# MTV5Beta.net
KiCad netlist of a schematic drawn in EAGLE
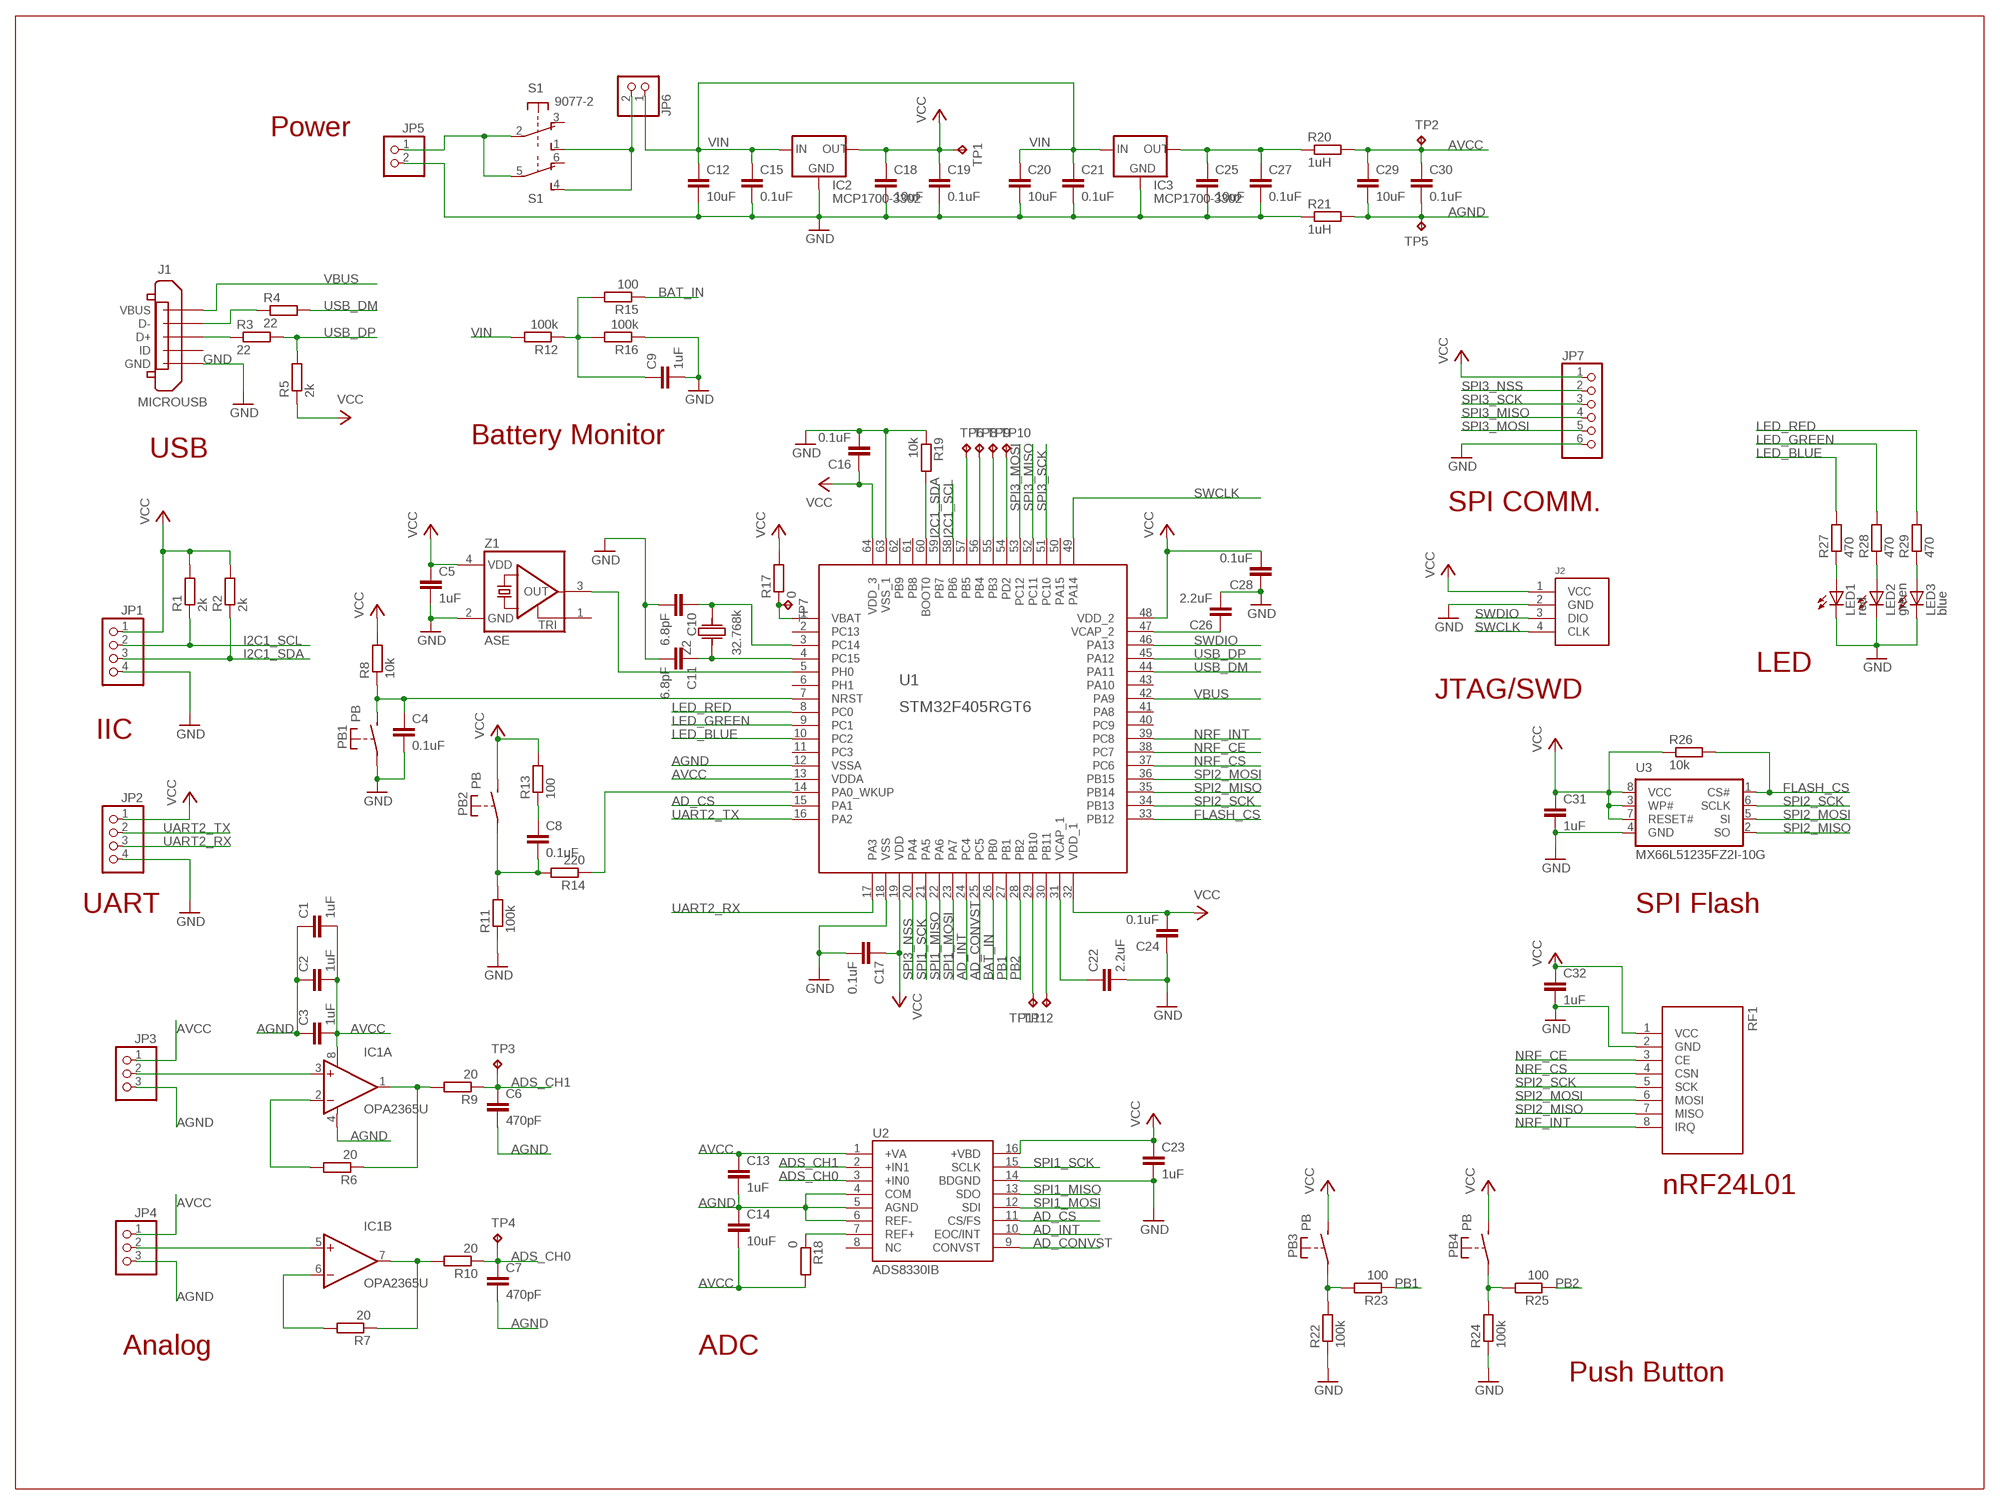
[diagram p0: schematic, sheet 1]

(export (version "E")
  (design (tool "Eeschema 10.0.6"))
  (components
    (comp (ref "C1")
      (value "1uF")
      (footprint "eagle-import:C0603")
      (libsource (lib "eagle-import") (part "C-EUC0603"))
    )
    (comp (ref "C2")
      (value "1uF")
      (footprint "eagle-import:C0603")
      (libsource (lib "eagle-import") (part "C-EUC0603"))
    )
    (comp (ref "C3")
      (value "1uF")
      (footprint "eagle-import:C0603")
      (libsource (lib "eagle-import") (part "C-EUC0603"))
    )
    (comp (ref "C4")
      (value "0.1uF")
      (footprint "eagle-import:C0603")
      (libsource (lib "eagle-import") (part "C-EUC0603"))
    )
    (comp (ref "C5")
      (value "1uF")
      (footprint "eagle-import:C0603")
      (libsource (lib "eagle-import") (part "C-EUC0603"))
    )
    (comp (ref "C6")
      (value "470pF")
      (footprint "eagle-import:C0603")
      (libsource (lib "eagle-import") (part "C-EUC0603"))
    )
    (comp (ref "C7")
      (value "470pF")
      (footprint "eagle-import:C0603")
      (libsource (lib "eagle-import") (part "C-EUC0603"))
    )
    (comp (ref "C8")
      (value "0.1uF")
      (footprint "eagle-import:C0603")
      (libsource (lib "eagle-import") (part "C-EUC0603"))
    )
    (comp (ref "C9")
      (value "1uF")
      (footprint "eagle-import:C0603")
      (libsource (lib "eagle-import") (part "C-EUC0603"))
    )
    (comp (ref "C10")
      (value "6.8pF")
      (footprint "eagle-import:C0603")
      (libsource (lib "eagle-import") (part "C-EUC0603"))
    )
    (comp (ref "C11")
      (value "6.8pF")
      (footprint "eagle-import:C0603")
      (libsource (lib "eagle-import") (part "C-EUC0603"))
    )
    (comp (ref "C12")
      (value "10uF")
      (footprint "eagle-import:C0603")
      (libsource (lib "eagle-import") (part "C-EUC0603"))
    )
    (comp (ref "C13")
      (value "1uF")
      (footprint "eagle-import:C0603")
      (libsource (lib "eagle-import") (part "C-EUC0603"))
    )
    (comp (ref "C14")
      (value "10uF")
      (footprint "eagle-import:C0603")
      (libsource (lib "eagle-import") (part "C-EUC0603"))
    )
    (comp (ref "C15")
      (value "0.1uF")
      (footprint "eagle-import:C0603")
      (libsource (lib "eagle-import") (part "C-EUC0603"))
    )
    (comp (ref "C16")
      (value "0.1uF")
      (footprint "eagle-import:C0603")
      (libsource (lib "eagle-import") (part "C-EUC0603"))
    )
    (comp (ref "C17")
      (value "0.1uF")
      (footprint "eagle-import:C0603")
      (libsource (lib "eagle-import") (part "C-EUC0603"))
    )
    (comp (ref "C18")
      (value "10uF")
      (footprint "eagle-import:C0603")
      (libsource (lib "eagle-import") (part "C-EUC0603"))
    )
    (comp (ref "C19")
      (value "0.1uF")
      (footprint "eagle-import:C0603")
      (libsource (lib "eagle-import") (part "C-EUC0603"))
    )
    (comp (ref "C20")
      (value "10uF")
      (footprint "eagle-import:C0603")
      (libsource (lib "eagle-import") (part "C-EUC0603"))
    )
    (comp (ref "C21")
      (value "0.1uF")
      (footprint "eagle-import:C0603")
      (libsource (lib "eagle-import") (part "C-EUC0603"))
    )
    (comp (ref "C22")
      (value "2.2uF")
      (footprint "eagle-import:C0603")
      (libsource (lib "eagle-import") (part "C-EUC0603"))
    )
    (comp (ref "C23")
      (value "1uF")
      (footprint "eagle-import:C0603")
      (libsource (lib "eagle-import") (part "C-EUC0603"))
    )
    (comp (ref "C24")
      (value "0.1uF")
      (footprint "eagle-import:C0603")
      (libsource (lib "eagle-import") (part "C-EUC0603"))
    )
    (comp (ref "C25")
      (value "10uF")
      (footprint "eagle-import:C0603")
      (libsource (lib "eagle-import") (part "C-EUC0603"))
    )
    (comp (ref "C26")
      (value "2.2uF")
      (footprint "eagle-import:C0603")
      (libsource (lib "eagle-import") (part "C-EUC0603"))
    )
    (comp (ref "C27")
      (value "0.1uF")
      (footprint "eagle-import:C0603")
      (libsource (lib "eagle-import") (part "C-EUC0603"))
    )
    (comp (ref "C28")
      (value "0.1uF")
      (footprint "eagle-import:C0603")
      (libsource (lib "eagle-import") (part "C-EUC0603"))
    )
    (comp (ref "C29")
      (value "10uF")
      (footprint "eagle-import:C0603")
      (libsource (lib "eagle-import") (part "C-EUC0603"))
    )
    (comp (ref "C30")
      (value "0.1uF")
      (footprint "eagle-import:C0603")
      (libsource (lib "eagle-import") (part "C-EUC0603"))
    )
    (comp (ref "C31")
      (value "1uF")
      (footprint "eagle-import:C0603")
      (libsource (lib "eagle-import") (part "C-EUC0603"))
    )
    (comp (ref "C32")
      (value "1uF")
      (footprint "eagle-import:C0603")
      (libsource (lib "eagle-import") (part "C-EUC0603"))
    )
    (comp (ref "IC1")
      (value "OPA2365U")
      (footprint "eagle-import:SO08")
      (fields (field (name "MF") "TEXAS INSTRUMENTS") (field (name "MPN") "OPA2134UA"))
      (libsource (lib "eagle-import") (part "OPA2365U"))
    )
    (comp (ref "IC2")
      (value "MCP1700-3302")
      (footprint "eagle-import:SOT23")
      (libsource (lib "eagle-import") (part "XC63FPM"))
    )
    (comp (ref "IC3")
      (value "MCP1700-3302")
      (footprint "eagle-import:SOT23")
      (libsource (lib "eagle-import") (part "XC63FPM"))
    )
    (comp (ref "J1")
      (value "MICROUSB")
      (footprint "eagle-import:MOLEX47346")
      (libsource (lib "eagle-import") (part "MICROUSB"))
    )
    (comp (ref "J2")
      (value "SWDPORT")
      (footprint "eagle-import:125-4P")
      (libsource (lib "eagle-import") (part "SWDPORT"))
    )
    (comp (ref "JP1")
      (value "PINHD-1X4")
      (footprint "eagle-import:1X04")
      (libsource (lib "eagle-import") (part "PINHD-1X4"))
    )
    (comp (ref "JP2")
      (value "PINHD-1X4")
      (footprint "eagle-import:1X04")
      (libsource (lib "eagle-import") (part "PINHD-1X4"))
    )
    (comp (ref "JP3")
      (value "PINHD-1X3")
      (footprint "eagle-import:1X03")
      (libsource (lib "eagle-import") (part "PINHD-1X3"))
    )
    (comp (ref "JP4")
      (value "PINHD-1X3")
      (footprint "eagle-import:1X03")
      (libsource (lib "eagle-import") (part "PINHD-1X3"))
    )
    (comp (ref "JP5")
      (value "PINHD-1X2")
      (footprint "eagle-import:1X02")
      (libsource (lib "eagle-import") (part "PINHD-1X2"))
    )
    (comp (ref "JP6")
      (value "PINHD-1X2")
      (footprint "eagle-import:1X02")
      (libsource (lib "eagle-import") (part "PINHD-1X2"))
    )
    (comp (ref "JP7")
      (value "PINHD-1X6")
      (footprint "eagle-import:1X06")
      (libsource (lib "eagle-import") (part "PINHD-1X6"))
    )
    (comp (ref "LED1")
      (value "red")
      (footprint "eagle-import:CHIP-LED0805")
      (libsource (lib "eagle-import") (part "LEDCHIP-LED0805"))
    )
    (comp (ref "LED2")
      (value "green")
      (footprint "eagle-import:CHIP-LED0805")
      (libsource (lib "eagle-import") (part "LEDCHIP-LED0805"))
    )
    (comp (ref "LED3")
      (value "blue")
      (footprint "eagle-import:CHIP-LED0805")
      (libsource (lib "eagle-import") (part "LEDCHIP-LED0805"))
    )
    (comp (ref "PB1")
      (value "PB")
      (footprint "eagle-import:BUTTON")
      (libsource (lib "eagle-import") (part "PB"))
    )
    (comp (ref "PB2")
      (value "PB")
      (footprint "eagle-import:BUTTON")
      (libsource (lib "eagle-import") (part "PB"))
    )
    (comp (ref "PB3")
      (value "PB")
      (footprint "eagle-import:BUTTON")
      (libsource (lib "eagle-import") (part "PB"))
    )
    (comp (ref "PB4")
      (value "PB")
      (footprint "eagle-import:BUTTON")
      (libsource (lib "eagle-import") (part "PB"))
    )
    (comp (ref "R1")
      (value "2k")
      (footprint "eagle-import:R0603")
      (libsource (lib "eagle-import") (part "R-EU_R0603"))
    )
    (comp (ref "R2")
      (value "2k")
      (footprint "eagle-import:R0603")
      (libsource (lib "eagle-import") (part "R-EU_R0603"))
    )
    (comp (ref "R3")
      (value "22")
      (footprint "eagle-import:R0603")
      (libsource (lib "eagle-import") (part "R-EU_R0603"))
    )
    (comp (ref "R4")
      (value "22")
      (footprint "eagle-import:R0603")
      (libsource (lib "eagle-import") (part "R-EU_R0603"))
    )
    (comp (ref "R5")
      (value "2k")
      (footprint "eagle-import:R0603")
      (libsource (lib "eagle-import") (part "R-EU_R0603"))
    )
    (comp (ref "R6")
      (value "20")
      (footprint "eagle-import:R0603")
      (libsource (lib "eagle-import") (part "R-EU_R0603"))
    )
    (comp (ref "R7")
      (value "20")
      (footprint "eagle-import:R0603")
      (libsource (lib "eagle-import") (part "R-EU_R0603"))
    )
    (comp (ref "R8")
      (value "10k")
      (footprint "eagle-import:R0603")
      (libsource (lib "eagle-import") (part "R-EU_R0603"))
    )
    (comp (ref "R9")
      (value "20")
      (footprint "eagle-import:R0603")
      (libsource (lib "eagle-import") (part "R-EU_R0603"))
    )
    (comp (ref "R10")
      (value "20")
      (footprint "eagle-import:R0603")
      (libsource (lib "eagle-import") (part "R-EU_R0603"))
    )
    (comp (ref "R11")
      (value "100k")
      (footprint "eagle-import:R0603")
      (libsource (lib "eagle-import") (part "R-EU_R0603"))
    )
    (comp (ref "R12")
      (value "100k")
      (footprint "eagle-import:R0603")
      (libsource (lib "eagle-import") (part "R-EU_R0603"))
    )
    (comp (ref "R13")
      (value "100")
      (footprint "eagle-import:R0603")
      (libsource (lib "eagle-import") (part "R-EU_R0603"))
    )
    (comp (ref "R14")
      (value "220")
      (footprint "eagle-import:R0603")
      (libsource (lib "eagle-import") (part "R-EU_R0603"))
    )
    (comp (ref "R15")
      (value "100")
      (footprint "eagle-import:R0603")
      (libsource (lib "eagle-import") (part "R-EU_R0603"))
    )
    (comp (ref "R16")
      (value "100k")
      (footprint "eagle-import:R0603")
      (libsource (lib "eagle-import") (part "R-EU_R0603"))
    )
    (comp (ref "R17")
      (value "0")
      (footprint "eagle-import:R0603")
      (libsource (lib "eagle-import") (part "R-EU_R0603"))
    )
    (comp (ref "R18")
      (value "0")
      (footprint "eagle-import:R0603")
      (libsource (lib "eagle-import") (part "R-EU_R0603"))
    )
    (comp (ref "R19")
      (value "10k")
      (footprint "eagle-import:R0603")
      (libsource (lib "eagle-import") (part "R-EU_R0603"))
    )
    (comp (ref "R20")
      (value "1uH")
      (footprint "eagle-import:R0603")
      (libsource (lib "eagle-import") (part "R-EU_R0603"))
    )
    (comp (ref "R21")
      (value "1uH")
      (footprint "eagle-import:R0603")
      (libsource (lib "eagle-import") (part "R-EU_R0603"))
    )
    (comp (ref "R22")
      (value "100k")
      (footprint "eagle-import:R0603")
      (libsource (lib "eagle-import") (part "R-EU_R0603"))
    )
    (comp (ref "R23")
      (value "100")
      (footprint "eagle-import:R0603")
      (libsource (lib "eagle-import") (part "R-EU_R0603"))
    )
    (comp (ref "R24")
      (value "100k")
      (footprint "eagle-import:R0603")
      (libsource (lib "eagle-import") (part "R-EU_R0603"))
    )
    (comp (ref "R25")
      (value "100")
      (footprint "eagle-import:R0603")
      (libsource (lib "eagle-import") (part "R-EU_R0603"))
    )
    (comp (ref "R26")
      (value "10k")
      (footprint "eagle-import:R0603")
      (libsource (lib "eagle-import") (part "R-EU_R0603"))
    )
    (comp (ref "R27")
      (value "470")
      (footprint "eagle-import:R0603")
      (libsource (lib "eagle-import") (part "R-EU_R0603"))
    )
    (comp (ref "R28")
      (value "470")
      (footprint "eagle-import:R0603")
      (libsource (lib "eagle-import") (part "R-EU_R0603"))
    )
    (comp (ref "R29")
      (value "470")
      (footprint "eagle-import:R0603")
      (libsource (lib "eagle-import") (part "R-EU_R0603"))
    )
    (comp (ref "RF1")
      (value "NRF24L01")
      (footprint "eagle-import:NRF24L01-MINI")
      (libsource (lib "eagle-import") (part "NRF24L01"))
    )
    (comp (ref "S1")
      (value "9077-2")
      (footprint "eagle-import:9077-2")
      (libsource (lib "eagle-import") (part "9077-2"))
    )
    (comp (ref "TP1")
      (value "TPB1,27")
      (footprint "eagle-import:B1,27")
      (libsource (lib "eagle-import") (part "TPB1,27"))
    )
    (comp (ref "TP2")
      (value "TPB1,27")
      (footprint "eagle-import:B1,27")
      (libsource (lib "eagle-import") (part "TPB1,27"))
    )
    (comp (ref "TP3")
      (value "TPB1,27")
      (footprint "eagle-import:B1,27")
      (libsource (lib "eagle-import") (part "TPB1,27"))
    )
    (comp (ref "TP4")
      (value "TPB1,27")
      (footprint "eagle-import:B1,27")
      (libsource (lib "eagle-import") (part "TPB1,27"))
    )
    (comp (ref "TP5")
      (value "TPB1,27")
      (footprint "eagle-import:B1,27")
      (libsource (lib "eagle-import") (part "TPB1,27"))
    )
    (comp (ref "TP6")
      (value "TPB1,27")
      (footprint "eagle-import:B1,27")
      (libsource (lib "eagle-import") (part "TPB1,27"))
    )
    (comp (ref "TP7")
      (value "TPB1,27")
      (footprint "eagle-import:B1,27")
      (libsource (lib "eagle-import") (part "TPB1,27"))
    )
    (comp (ref "TP8")
      (value "TPB1,27")
      (footprint "eagle-import:B1,27")
      (libsource (lib "eagle-import") (part "TPB1,27"))
    )
    (comp (ref "TP9")
      (value "TPB1,27")
      (footprint "eagle-import:B1,27")
      (libsource (lib "eagle-import") (part "TPB1,27"))
    )
    (comp (ref "TP10")
      (value "TPB1,27")
      (footprint "eagle-import:B1,27")
      (libsource (lib "eagle-import") (part "TPB1,27"))
    )
    (comp (ref "TP11")
      (value "TPB1,27")
      (footprint "eagle-import:B1,27")
      (libsource (lib "eagle-import") (part "TPB1,27"))
    )
    (comp (ref "TP12")
      (value "TPB1,27")
      (footprint "eagle-import:B1,27")
      (libsource (lib "eagle-import") (part "TPB1,27"))
    )
    (comp (ref "U1")
      (value "STM32F405RGT6")
      (footprint "eagle-import:LQFP64")
      (libsource (lib "eagle-import") (part "STM32F405RGT6"))
    )
    (comp (ref "U2")
      (value "ADS8330IB")
      (footprint "eagle-import:TSSOP16")
      (libsource (lib "eagle-import") (part "ADS8330IB"))
    )
    (comp (ref "U3")
      (value "MX66L51235FZ2I-10G")
      (footprint "eagle-import:WSON8L")
      (libsource (lib "eagle-import") (part "MX66L51235FZ2I-10G"))
    )
    (comp (ref "Z1")
      (value "ASE")
      (footprint "eagle-import:ASE")
      (libsource (lib "eagle-import") (part "ASE"))
    )
    (comp (ref "Z2")
      (value "32.768k")
      (footprint "eagle-import:CM315")
      (libsource (lib "eagle-import") (part "CRYSTAL-CM315"))
    )
  )
  (nets
    (net (code "1") (name "/ADS_CH0") (class "Default")
      (node (ref "C7") (pin "1") (pinfunction "1_1") (pintype "passive"))
      (node (ref "R10") (pin "1") (pinfunction "1_1") (pintype "passive"))
      (node (ref "TP4") (pin "TP") (pinfunction "TP_TP") (pintype "input"))
      (node (ref "U2") (pin "3") (pinfunction "+IN0_3") (pintype "bidirectional"))
    )
    (net (code "2") (name "/ADS_CH1") (class "Default")
      (node (ref "C6") (pin "1") (pinfunction "1_1") (pintype "passive"))
      (node (ref "R9") (pin "1") (pinfunction "1_1") (pintype "passive"))
      (node (ref "TP3") (pin "TP") (pinfunction "TP_TP") (pintype "input"))
      (node (ref "U2") (pin "2") (pinfunction "+IN1_2") (pintype "bidirectional"))
    )
    (net (code "3") (name "/AD_CONVST") (class "Default")
      (node (ref "U1") (pin "25") (pinfunction "PC5_25") (pintype "bidirectional"))
      (node (ref "U2") (pin "9") (pinfunction "CONVST_9") (pintype "bidirectional"))
    )
    (net (code "4") (name "/AD_CS") (class "Default")
      (node (ref "U1") (pin "15") (pinfunction "PA1_15") (pintype "bidirectional"))
      (node (ref "U2") (pin "11") (pinfunction "CS/FS_11") (pintype "bidirectional"))
    )
    (net (code "5") (name "/AD_INT") (class "Default")
      (node (ref "U1") (pin "24") (pinfunction "PC4_24") (pintype "bidirectional"))
      (node (ref "U2") (pin "10") (pinfunction "EOC/INT_10") (pintype "bidirectional"))
    )
    (net (code "6") (name "/AGND") (class "Default")
      (node (ref "C1") (pin "1") (pinfunction "1_1") (pintype "passive"))
      (node (ref "C13") (pin "2") (pinfunction "2_2") (pintype "passive"))
      (node (ref "C14") (pin "1") (pinfunction "1_1") (pintype "passive"))
      (node (ref "C2") (pin "1") (pinfunction "1_1") (pintype "passive"))
      (node (ref "C29") (pin "2") (pinfunction "2_2") (pintype "passive"))
      (node (ref "C3") (pin "1") (pinfunction "1_1") (pintype "passive"))
      (node (ref "C30") (pin "2") (pinfunction "2_2") (pintype "passive"))
      (node (ref "C6") (pin "2") (pinfunction "2_2") (pintype "passive"))
      (node (ref "C7") (pin "2") (pinfunction "2_2") (pintype "passive"))
      (node (ref "IC1") (pin "4") (pinfunction "V-_4") (pintype "power_in"))
      (node (ref "JP3") (pin "3") (pinfunction "3_3") (pintype "passive"))
      (node (ref "JP4") (pin "3") (pinfunction "3_3") (pintype "passive"))
      (node (ref "R21") (pin "2") (pinfunction "2_2") (pintype "passive"))
      (node (ref "TP5") (pin "TP") (pinfunction "TP_TP") (pintype "input"))
      (node (ref "U1") (pin "12") (pinfunction "VSSA_12") (pintype "bidirectional"))
      (node (ref "U2") (pin "4") (pinfunction "COM_4") (pintype "bidirectional"))
      (node (ref "U2") (pin "5") (pinfunction "AGND_5") (pintype "power_in"))
      (node (ref "U2") (pin "6") (pinfunction "REF-_6") (pintype "bidirectional"))
    )
    (net (code "7") (name "/AVCC") (class "Default")
      (node (ref "C1") (pin "2") (pinfunction "2_2") (pintype "passive"))
      (node (ref "C13") (pin "1") (pinfunction "1_1") (pintype "passive"))
      (node (ref "C14") (pin "2") (pinfunction "2_2") (pintype "passive"))
      (node (ref "C2") (pin "2") (pinfunction "2_2") (pintype "passive"))
      (node (ref "C29") (pin "1") (pinfunction "1_1") (pintype "passive"))
      (node (ref "C3") (pin "2") (pinfunction "2_2") (pintype "passive"))
      (node (ref "C30") (pin "1") (pinfunction "1_1") (pintype "passive"))
      (node (ref "IC1") (pin "8") (pinfunction "V+_8") (pintype "power_in"))
      (node (ref "JP3") (pin "1") (pinfunction "1_1") (pintype "passive"))
      (node (ref "JP4") (pin "1") (pinfunction "1_1") (pintype "passive"))
      (node (ref "R18") (pin "2") (pinfunction "2_2") (pintype "passive"))
      (node (ref "R20") (pin "2") (pinfunction "2_2") (pintype "passive"))
      (node (ref "TP2") (pin "TP") (pinfunction "TP_TP") (pintype "input"))
      (node (ref "U1") (pin "13") (pinfunction "VDDA_13") (pintype "bidirectional"))
      (node (ref "U2") (pin "1") (pinfunction "+VA_1") (pintype "power_in"))
    )
    (net (code "8") (name "/BAT_IN") (class "Default")
      (node (ref "R15") (pin "1") (pinfunction "1_1") (pintype "passive"))
      (node (ref "U1") (pin "26") (pinfunction "PB0_26") (pintype "bidirectional"))
    )
    (net (code "9") (name "/FLASH_CS") (class "Default")
      (node (ref "R26") (pin "2") (pinfunction "2_2") (pintype "passive"))
      (node (ref "U1") (pin "33") (pinfunction "PB12_33") (pintype "bidirectional"))
      (node (ref "U3") (pin "1") (pinfunction "CS#_1") (pintype "bidirectional"))
    )
    (net (code "10") (name "/I2C1_SCL") (class "Default")
      (node (ref "JP1") (pin "2") (pinfunction "2_2") (pintype "passive"))
      (node (ref "R1") (pin "1") (pinfunction "1_1") (pintype "passive"))
      (node (ref "U1") (pin "58") (pinfunction "PB6_58") (pintype "bidirectional"))
    )
    (net (code "11") (name "/I2C1_SDA") (class "Default")
      (node (ref "JP1") (pin "3") (pinfunction "3_3") (pintype "passive"))
      (node (ref "R2") (pin "1") (pinfunction "1_1") (pintype "passive"))
      (node (ref "U1") (pin "59") (pinfunction "PB7_59") (pintype "bidirectional"))
    )
    (net (code "12") (name "/LED_BLUE") (class "Default")
      (node (ref "R27") (pin "2") (pinfunction "2_2") (pintype "passive"))
      (node (ref "U1") (pin "10") (pinfunction "PC2_10") (pintype "bidirectional"))
    )
    (net (code "13") (name "/LED_GREEN") (class "Default")
      (node (ref "R28") (pin "2") (pinfunction "2_2") (pintype "passive"))
      (node (ref "U1") (pin "9") (pinfunction "PC1_9") (pintype "bidirectional"))
    )
    (net (code "14") (name "/LED_RED") (class "Default")
      (node (ref "R29") (pin "2") (pinfunction "2_2") (pintype "passive"))
      (node (ref "U1") (pin "8") (pinfunction "PC0_8") (pintype "bidirectional"))
    )
    (net (code "15") (name "/NRF_CE") (class "Default")
      (node (ref "RF1") (pin "3") (pinfunction "CE_3") (pintype "bidirectional"))
      (node (ref "U1") (pin "38") (pinfunction "PC7_38") (pintype "bidirectional"))
    )
    (net (code "16") (name "/NRF_CS") (class "Default")
      (node (ref "RF1") (pin "4") (pinfunction "CSN_4") (pintype "bidirectional"))
      (node (ref "U1") (pin "37") (pinfunction "PC6_37") (pintype "bidirectional"))
    )
    (net (code "17") (name "/NRF_INT") (class "Default")
      (node (ref "RF1") (pin "8") (pinfunction "IRQ_8") (pintype "bidirectional"))
      (node (ref "U1") (pin "39") (pinfunction "PC8_39") (pintype "bidirectional"))
    )
    (net (code "18") (name "/PB1") (class "Default")
      (node (ref "R23") (pin "1") (pinfunction "1_1") (pintype "passive"))
      (node (ref "U1") (pin "27") (pinfunction "PB1_27") (pintype "bidirectional"))
    )
    (net (code "19") (name "/PB2") (class "Default")
      (node (ref "R25") (pin "1") (pinfunction "1_1") (pintype "passive"))
      (node (ref "U1") (pin "28") (pinfunction "PB2_28") (pintype "bidirectional"))
    )
    (net (code "20") (name "/SPI1_MISO") (class "Default")
      (node (ref "U1") (pin "22") (pinfunction "PA6_22") (pintype "bidirectional"))
      (node (ref "U2") (pin "13") (pinfunction "SDO_13") (pintype "bidirectional"))
    )
    (net (code "21") (name "/SPI1_MOSI") (class "Default")
      (node (ref "U1") (pin "23") (pinfunction "PA7_23") (pintype "bidirectional"))
      (node (ref "U2") (pin "12") (pinfunction "SDI_12") (pintype "bidirectional"))
    )
    (net (code "22") (name "/SPI1_SCK") (class "Default")
      (node (ref "U1") (pin "21") (pinfunction "PA5_21") (pintype "bidirectional"))
      (node (ref "U2") (pin "15") (pinfunction "SCLK_15") (pintype "bidirectional"))
    )
    (net (code "23") (name "/SPI2_MISO") (class "Default")
      (node (ref "RF1") (pin "7") (pinfunction "MISO_7") (pintype "bidirectional"))
      (node (ref "U1") (pin "35") (pinfunction "PB14_35") (pintype "bidirectional"))
      (node (ref "U3") (pin "2") (pinfunction "SO_2") (pintype "bidirectional"))
    )
    (net (code "24") (name "/SPI2_MOSI") (class "Default")
      (node (ref "RF1") (pin "6") (pinfunction "MOSI_6") (pintype "bidirectional"))
      (node (ref "U1") (pin "36") (pinfunction "PB15_36") (pintype "bidirectional"))
      (node (ref "U3") (pin "5") (pinfunction "SI_5") (pintype "bidirectional"))
    )
    (net (code "25") (name "/SPI2_SCK") (class "Default")
      (node (ref "RF1") (pin "5") (pinfunction "SCK_5") (pintype "bidirectional"))
      (node (ref "U1") (pin "34") (pinfunction "PB13_34") (pintype "bidirectional"))
      (node (ref "U3") (pin "6") (pinfunction "SCLK_6") (pintype "bidirectional"))
    )
    (net (code "26") (name "/SPI3_MISO") (class "Default")
      (node (ref "JP7") (pin "4") (pinfunction "4_4") (pintype "passive"))
      (node (ref "U1") (pin "52") (pinfunction "PC11_52") (pintype "bidirectional"))
    )
    (net (code "27") (name "/SPI3_MOSI") (class "Default")
      (node (ref "JP7") (pin "5") (pinfunction "5_5") (pintype "passive"))
      (node (ref "U1") (pin "53") (pinfunction "PC12_53") (pintype "bidirectional"))
    )
    (net (code "28") (name "/SPI3_NSS") (class "Default")
      (node (ref "JP7") (pin "2") (pinfunction "2_2") (pintype "passive"))
      (node (ref "U1") (pin "20") (pinfunction "PA4_20") (pintype "bidirectional"))
    )
    (net (code "29") (name "/SPI3_SCK") (class "Default")
      (node (ref "JP7") (pin "3") (pinfunction "3_3") (pintype "passive"))
      (node (ref "U1") (pin "51") (pinfunction "PC10_51") (pintype "bidirectional"))
    )
    (net (code "30") (name "/SWCLK") (class "Default")
      (node (ref "J2") (pin "4") (pinfunction "CLK_4") (pintype "bidirectional"))
      (node (ref "U1") (pin "49") (pinfunction "PA14_49") (pintype "bidirectional"))
    )
    (net (code "31") (name "/SWDIO") (class "Default")
      (node (ref "J2") (pin "3") (pinfunction "DIO_3") (pintype "bidirectional"))
      (node (ref "U1") (pin "46") (pinfunction "PA13_46") (pintype "bidirectional"))
    )
    (net (code "32") (name "/UART2_RX") (class "Default")
      (node (ref "JP2") (pin "3") (pinfunction "3_3") (pintype "passive"))
      (node (ref "U1") (pin "17") (pinfunction "PA3_17") (pintype "bidirectional"))
    )
    (net (code "33") (name "/UART2_TX") (class "Default")
      (node (ref "JP2") (pin "2") (pinfunction "2_2") (pintype "passive"))
      (node (ref "U1") (pin "16") (pinfunction "PA2_16") (pintype "bidirectional"))
    )
    (net (code "34") (name "/USB_DM") (class "Default")
      (node (ref "R4") (pin "2") (pinfunction "2_2") (pintype "passive"))
      (node (ref "U1") (pin "44") (pinfunction "PA11_44") (pintype "bidirectional"))
    )
    (net (code "35") (name "/USB_DP") (class "Default")
      (node (ref "R3") (pin "2") (pinfunction "2_2") (pintype "passive"))
      (node (ref "R5") (pin "2") (pinfunction "2_2") (pintype "passive"))
      (node (ref "U1") (pin "45") (pinfunction "PA12_45") (pintype "bidirectional"))
    )
    (net (code "36") (name "/VBUS") (class "Default")
      (node (ref "J1") (pin "1") (pinfunction "VBUS_1") (pintype "passive"))
      (node (ref "U1") (pin "42") (pinfunction "PA9_42") (pintype "bidirectional"))
    )
    (net (code "37") (name "/VIN") (class "Default")
      (node (ref "C12") (pin "1") (pinfunction "1_1") (pintype "passive"))
      (node (ref "C15") (pin "1") (pinfunction "1_1") (pintype "passive"))
      (node (ref "C20") (pin "1") (pinfunction "1_1") (pintype "passive"))
      (node (ref "C21") (pin "1") (pinfunction "1_1") (pintype "passive"))
      (node (ref "IC2") (pin "3") (pinfunction "IN_3") (pintype "input"))
      (node (ref "IC3") (pin "3") (pinfunction "IN_3") (pintype "input"))
      (node (ref "JP6") (pin "1") (pinfunction "1_1") (pintype "passive"))
      (node (ref "R12") (pin "2") (pinfunction "2_2") (pintype "passive"))
    )
    (net (code "38") (name "GND") (class "Default")
      (node (ref "C10") (pin "2") (pinfunction "2_2") (pintype "passive"))
      (node (ref "C11") (pin "2") (pinfunction "2_2") (pintype "passive"))
      (node (ref "C12") (pin "2") (pinfunction "2_2") (pintype "passive"))
      (node (ref "C15") (pin "2") (pinfunction "2_2") (pintype "passive"))
      (node (ref "C16") (pin "2") (pinfunction "2_2") (pintype "passive"))
      (node (ref "C17") (pin "2") (pinfunction "2_2") (pintype "passive"))
      (node (ref "C18") (pin "2") (pinfunction "2_2") (pintype "passive"))
      (node (ref "C19") (pin "2") (pinfunction "2_2") (pintype "passive"))
      (node (ref "C20") (pin "2") (pinfunction "2_2") (pintype "passive"))
      (node (ref "C21") (pin "2") (pinfunction "2_2") (pintype "passive"))
      (node (ref "C22") (pin "2") (pinfunction "2_2") (pintype "passive"))
      (node (ref "C23") (pin "2") (pinfunction "2_2") (pintype "passive"))
      (node (ref "C24") (pin "1") (pinfunction "1_1") (pintype "passive"))
      (node (ref "C25") (pin "2") (pinfunction "2_2") (pintype "passive"))
      (node (ref "C26") (pin "2") (pinfunction "2_2") (pintype "passive"))
      (node (ref "C27") (pin "2") (pinfunction "2_2") (pintype "passive"))
      (node (ref "C28") (pin "1") (pinfunction "1_1") (pintype "passive"))
      (node (ref "C31") (pin "2") (pinfunction "2_2") (pintype "passive"))
      (node (ref "C32") (pin "2") (pinfunction "2_2") (pintype "passive"))
      (node (ref "C4") (pin "2") (pinfunction "2_2") (pintype "passive"))
      (node (ref "C5") (pin "2") (pinfunction "2_2") (pintype "passive"))
      (node (ref "C9") (pin "2") (pinfunction "2_2") (pintype "passive"))
      (node (ref "IC2") (pin "1") (pinfunction "GND_1") (pintype "input"))
      (node (ref "IC3") (pin "1") (pinfunction "GND_1") (pintype "input"))
      (node (ref "J1") (pin "5") (pinfunction "GND_5") (pintype "passive"))
      (node (ref "J2") (pin "2") (pinfunction "GND_2") (pintype "power_in"))
      (node (ref "JP1") (pin "4") (pinfunction "4_4") (pintype "passive"))
      (node (ref "JP2") (pin "4") (pinfunction "4_4") (pintype "passive"))
      (node (ref "JP5") (pin "2") (pinfunction "2_2") (pintype "passive"))
      (node (ref "JP7") (pin "6") (pinfunction "6_6") (pintype "passive"))
      (node (ref "LED1") (pin "C") (pinfunction "C_C") (pintype "passive"))
      (node (ref "LED2") (pin "C") (pinfunction "C_C") (pintype "passive"))
      (node (ref "LED3") (pin "C") (pinfunction "C_C") (pintype "passive"))
      (node (ref "PB1") (pin "1") (pinfunction "P_1") (pintype "passive"))
      (node (ref "R11") (pin "1") (pinfunction "1_1") (pintype "passive"))
      (node (ref "R16") (pin "1") (pinfunction "1_1") (pintype "passive"))
      (node (ref "R19") (pin "1") (pinfunction "1_1") (pintype "passive"))
      (node (ref "R21") (pin "1") (pinfunction "1_1") (pintype "passive"))
      (node (ref "R22") (pin "1") (pinfunction "1_1") (pintype "passive"))
      (node (ref "R24") (pin "1") (pinfunction "1_1") (pintype "passive"))
      (node (ref "RF1") (pin "2") (pinfunction "GND_2") (pintype "bidirectional"))
      (node (ref "U1") (pin "18") (pinfunction "VSS_18") (pintype "bidirectional"))
      (node (ref "U1") (pin "63") (pinfunction "VSS_1_63") (pintype "bidirectional"))
      (node (ref "U2") (pin "14") (pinfunction "BDGND_14") (pintype "power_in"))
      (node (ref "U3") (pin "4") (pinfunction "GND_4") (pintype "bidirectional"))
      (node (ref "Z1") (pin "2") (pinfunction "GND_2") (pintype "power_in"))
    )
    (net (code "39") (name "Net-(C8-Pad1)") (class "Default")
      (node (ref "C8") (pin "1") (pinfunction "1_1") (pintype "passive"))
      (node (ref "R13") (pin "1") (pinfunction "1_1") (pintype "passive"))
    )
    (net (code "40") (name "Net-(C9-Pad1)") (class "Default")
      (node (ref "C9") (pin "1") (pinfunction "1_1") (pintype "passive"))
      (node (ref "R12") (pin "1") (pinfunction "1_1") (pintype "passive"))
      (node (ref "R15") (pin "2") (pinfunction "2_2") (pintype "passive"))
      (node (ref "R16") (pin "2") (pinfunction "2_2") (pintype "passive"))
    )
    (net (code "41") (name "Net-(IC1A-+IN)") (class "Default")
      (node (ref "IC1") (pin "3") (pinfunction "+IN_3") (pintype "input"))
      (node (ref "JP3") (pin "2") (pinfunction "2_2") (pintype "passive"))
    )
    (net (code "42") (name "Net-(IC1A--IN)") (class "Default")
      (node (ref "IC1") (pin "2") (pinfunction "-IN_2") (pintype "input"))
      (node (ref "R6") (pin "2") (pinfunction "2_2") (pintype "passive"))
    )
    (net (code "43") (name "Net-(IC1A-OUT)") (class "Default")
      (node (ref "IC1") (pin "1") (pinfunction "OUT_1") (pintype "output"))
      (node (ref "R6") (pin "1") (pinfunction "1_1") (pintype "passive"))
      (node (ref "R9") (pin "2") (pinfunction "2_2") (pintype "passive"))
    )
    (net (code "44") (name "Net-(IC1B-+IN)") (class "Default")
      (node (ref "IC1") (pin "5") (pinfunction "+IN_5") (pintype "input"))
      (node (ref "JP4") (pin "2") (pinfunction "2_2") (pintype "passive"))
    )
    (net (code "45") (name "Net-(IC1B--IN)") (class "Default")
      (node (ref "IC1") (pin "6") (pinfunction "-IN_6") (pintype "input"))
      (node (ref "R7") (pin "2") (pinfunction "2_2") (pintype "passive"))
    )
    (net (code "46") (name "Net-(IC1B-OUT)") (class "Default")
      (node (ref "IC1") (pin "7") (pinfunction "OUT_7") (pintype "output"))
      (node (ref "R10") (pin "2") (pinfunction "2_2") (pintype "passive"))
      (node (ref "R7") (pin "1") (pinfunction "1_1") (pintype "passive"))
    )
    (net (code "47") (name "Net-(IC3-OUT)") (class "Default")
      (node (ref "C25") (pin "1") (pinfunction "1_1") (pintype "passive"))
      (node (ref "C27") (pin "1") (pinfunction "1_1") (pintype "passive"))
      (node (ref "IC3") (pin "2") (pinfunction "OUT_2") (pintype "passive"))
      (node (ref "R20") (pin "1") (pinfunction "1_1") (pintype "passive"))
    )
    (net (code "48") (name "Net-(J1-D+)") (class "Default")
      (node (ref "J1") (pin "3") (pinfunction "D+_3") (pintype "passive"))
      (node (ref "R3") (pin "1") (pinfunction "1_1") (pintype "passive"))
    )
    (net (code "49") (name "Net-(J1-D-)") (class "Default")
      (node (ref "J1") (pin "2") (pinfunction "D-_2") (pintype "passive"))
      (node (ref "R4") (pin "1") (pinfunction "1_1") (pintype "passive"))
    )
    (net (code "50") (name "Net-(LED1-PadA)") (class "Default")
      (node (ref "LED1") (pin "A") (pinfunction "A_A") (pintype "passive"))
      (node (ref "R27") (pin "1") (pinfunction "1_1") (pintype "passive"))
    )
    (net (code "51") (name "Net-(LED2-PadA)") (class "Default")
      (node (ref "LED2") (pin "A") (pinfunction "A_A") (pintype "passive"))
      (node (ref "R28") (pin "1") (pinfunction "1_1") (pintype "passive"))
    )
    (net (code "52") (name "Net-(LED3-PadA)") (class "Default")
      (node (ref "LED3") (pin "A") (pinfunction "A_A") (pintype "passive"))
      (node (ref "R29") (pin "1") (pinfunction "1_1") (pintype "passive"))
    )
    (net (code "53") (name "Net-(PB1-S)") (class "Default")
      (node (ref "C4") (pin "1") (pinfunction "1_1") (pintype "passive"))
      (node (ref "PB1") (pin "2") (pinfunction "S_2") (pintype "passive"))
      (node (ref "R8") (pin "1") (pinfunction "1_1") (pintype "passive"))
      (node (ref "U1") (pin "7") (pinfunction "NRST_7") (pintype "bidirectional"))
    )
    (net (code "54") (name "Net-(PB2-P)") (class "Default")
      (node (ref "C8") (pin "2") (pinfunction "2_2") (pintype "passive"))
      (node (ref "PB2") (pin "1") (pinfunction "P_1") (pintype "passive"))
      (node (ref "R11") (pin "2") (pinfunction "2_2") (pintype "passive"))
      (node (ref "R14") (pin "2") (pinfunction "2_2") (pintype "passive"))
    )
    (net (code "55") (name "Net-(PB3-P)") (class "Default")
      (node (ref "PB3") (pin "1") (pinfunction "P_1") (pintype "passive"))
      (node (ref "R22") (pin "2") (pinfunction "2_2") (pintype "passive"))
      (node (ref "R23") (pin "2") (pinfunction "2_2") (pintype "passive"))
    )
    (net (code "56") (name "Net-(PB4-P)") (class "Default")
      (node (ref "PB4") (pin "1") (pinfunction "P_1") (pintype "passive"))
      (node (ref "R24") (pin "2") (pinfunction "2_2") (pintype "passive"))
      (node (ref "R25") (pin "2") (pinfunction "2_2") (pintype "passive"))
    )
    (net (code "57") (name "Net-(S1A-P)") (class "Default")
      (node (ref "JP5") (pin "1") (pinfunction "1_1") (pintype "passive"))
      (node (ref "S1") (pin "2") (pinfunction "P_2") (pintype "passive"))
      (node (ref "S1") (pin "5") (pinfunction "P_5") (pintype "passive"))
    )
    (net (code "58") (name "Net-(S1A-S)") (class "Default")
      (node (ref "JP6") (pin "2") (pinfunction "2_2") (pintype "passive"))
      (node (ref "S1") (pin "1") (pinfunction "S_1") (pintype "passive"))
      (node (ref "S1") (pin "4") (pinfunction "S_4") (pintype "passive"))
    )
    (net (code "59") (name "Net-(U1-BOOT0)") (class "Default")
      (node (ref "R19") (pin "2") (pinfunction "2_2") (pintype "passive"))
      (node (ref "U1") (pin "60") (pinfunction "BOOT0_60") (pintype "bidirectional"))
    )
    (net (code "60") (name "Net-(U1-PA0_WKUP)") (class "Default")
      (node (ref "R14") (pin "1") (pinfunction "1_1") (pintype "passive"))
      (node (ref "U1") (pin "14") (pinfunction "PA0_WKUP_14") (pintype "bidirectional"))
    )
    (net (code "61") (name "Net-(U1-PB3)") (class "Default")
      (node (ref "TP9") (pin "TP") (pinfunction "TP_TP") (pintype "input"))
      (node (ref "U1") (pin "55") (pinfunction "PB3_55") (pintype "bidirectional"))
    )
    (net (code "62") (name "Net-(U1-PB4)") (class "Default")
      (node (ref "TP8") (pin "TP") (pinfunction "TP_TP") (pintype "input"))
      (node (ref "U1") (pin "56") (pinfunction "PB4_56") (pintype "bidirectional"))
    )
    (net (code "63") (name "Net-(U1-PB5)") (class "Default")
      (node (ref "TP6") (pin "TP") (pinfunction "TP_TP") (pintype "input"))
      (node (ref "U1") (pin "57") (pinfunction "PB5_57") (pintype "bidirectional"))
    )
    (net (code "64") (name "Net-(U1-PB10)") (class "Default")
      (node (ref "TP11") (pin "TP") (pinfunction "TP_TP") (pintype "input"))
      (node (ref "U1") (pin "29") (pinfunction "PB10_29") (pintype "bidirectional"))
    )
    (net (code "65") (name "Net-(U1-PB11)") (class "Default")
      (node (ref "TP12") (pin "TP") (pinfunction "TP_TP") (pintype "input"))
      (node (ref "U1") (pin "30") (pinfunction "PB11_30") (pintype "bidirectional"))
    )
    (net (code "66") (name "Net-(U1-PC14)") (class "Default")
      (node (ref "C10") (pin "1") (pinfunction "1_1") (pintype "passive"))
      (node (ref "U1") (pin "3") (pinfunction "PC14_3") (pintype "bidirectional"))
      (node (ref "Z2") (pin "2") (pinfunction "X2_2") (pintype "bidirectional"))
    )
    (net (code "67") (name "Net-(U1-PC15)") (class "Default")
      (node (ref "C11") (pin "1") (pinfunction "1_1") (pintype "passive"))
      (node (ref "U1") (pin "4") (pinfunction "PC15_4") (pintype "bidirectional"))
      (node (ref "Z2") (pin "1") (pinfunction "X1_1") (pintype "bidirectional"))
    )
    (net (code "68") (name "Net-(U1-PD2)") (class "Default")
      (node (ref "TP10") (pin "TP") (pinfunction "TP_TP") (pintype "input"))
      (node (ref "U1") (pin "54") (pinfunction "PD2_54") (pintype "bidirectional"))
    )
    (net (code "69") (name "Net-(U1-PH0)") (class "Default")
      (node (ref "U1") (pin "5") (pinfunction "PH0_5") (pintype "bidirectional"))
      (node (ref "Z1") (pin "3") (pinfunction "OUT_3") (pintype "output"))
    )
    (net (code "70") (name "Net-(U1-VBAT)") (class "Default")
      (node (ref "R17") (pin "1") (pinfunction "1_1") (pintype "passive"))
      (node (ref "TP7") (pin "TP") (pinfunction "TP_TP") (pintype "input"))
      (node (ref "U1") (pin "1") (pinfunction "VBAT_1") (pintype "bidirectional"))
    )
    (net (code "71") (name "Net-(U1-VCAP_1)") (class "Default")
      (node (ref "C22") (pin "1") (pinfunction "1_1") (pintype "passive"))
      (node (ref "U1") (pin "31") (pinfunction "VCAP_1_31") (pintype "bidirectional"))
    )
    (net (code "72") (name "Net-(U1-VCAP_2)") (class "Default")
      (node (ref "C26") (pin "1") (pinfunction "1_1") (pintype "passive"))
      (node (ref "U1") (pin "47") (pinfunction "VCAP_2_47") (pintype "bidirectional"))
    )
    (net (code "73") (name "Net-(U2-REF+)") (class "Default")
      (node (ref "R18") (pin "1") (pinfunction "1_1") (pintype "passive"))
      (node (ref "U2") (pin "7") (pinfunction "REF+_7") (pintype "bidirectional"))
    )
    (net (code "74") (name "VCC") (class "Default")
      (node (ref "C16") (pin "1") (pinfunction "1_1") (pintype "passive"))
      (node (ref "C17") (pin "1") (pinfunction "1_1") (pintype "passive"))
      (node (ref "C18") (pin "1") (pinfunction "1_1") (pintype "passive"))
      (node (ref "C19") (pin "1") (pinfunction "1_1") (pintype "passive"))
      (node (ref "C23") (pin "1") (pinfunction "1_1") (pintype "passive"))
      (node (ref "C24") (pin "2") (pinfunction "2_2") (pintype "passive"))
      (node (ref "C28") (pin "2") (pinfunction "2_2") (pintype "passive"))
      (node (ref "C31") (pin "1") (pinfunction "1_1") (pintype "passive"))
      (node (ref "C32") (pin "1") (pinfunction "1_1") (pintype "passive"))
      (node (ref "C5") (pin "1") (pinfunction "1_1") (pintype "passive"))
      (node (ref "IC2") (pin "2") (pinfunction "OUT_2") (pintype "passive"))
      (node (ref "J2") (pin "1") (pinfunction "VCC_1") (pintype "power_in"))
      (node (ref "JP1") (pin "1") (pinfunction "1_1") (pintype "passive"))
      (node (ref "JP2") (pin "1") (pinfunction "1_1") (pintype "passive"))
      (node (ref "JP7") (pin "1") (pinfunction "1_1") (pintype "passive"))
      (node (ref "PB2") (pin "2") (pinfunction "S_2") (pintype "passive"))
      (node (ref "PB3") (pin "2") (pinfunction "S_2") (pintype "passive"))
      (node (ref "PB4") (pin "2") (pinfunction "S_2") (pintype "passive"))
      (node (ref "R1") (pin "2") (pinfunction "2_2") (pintype "passive"))
      (node (ref "R13") (pin "2") (pinfunction "2_2") (pintype "passive"))
      (node (ref "R17") (pin "2") (pinfunction "2_2") (pintype "passive"))
      (node (ref "R2") (pin "2") (pinfunction "2_2") (pintype "passive"))
      (node (ref "R26") (pin "1") (pinfunction "1_1") (pintype "passive"))
      (node (ref "R5") (pin "1") (pinfunction "1_1") (pintype "passive"))
      (node (ref "R8") (pin "2") (pinfunction "2_2") (pintype "passive"))
      (node (ref "RF1") (pin "1") (pinfunction "VCC_1") (pintype "bidirectional"))
      (node (ref "TP1") (pin "TP") (pinfunction "TP_TP") (pintype "input"))
      (node (ref "U1") (pin "19") (pinfunction "VDD_19") (pintype "bidirectional"))
      (node (ref "U1") (pin "32") (pinfunction "VDD_1_32") (pintype "bidirectional"))
      (node (ref "U1") (pin "48") (pinfunction "VDD_2_48") (pintype "bidirectional"))
      (node (ref "U1") (pin "64") (pinfunction "VDD_3_64") (pintype "bidirectional"))
      (node (ref "U2") (pin "16") (pinfunction "+VBD_16") (pintype "power_in"))
      (node (ref "U3") (pin "3") (pinfunction "WP#_3") (pintype "bidirectional"))
      (node (ref "U3") (pin "7") (pinfunction "RESET#_7") (pintype "bidirectional"))
      (node (ref "U3") (pin "8") (pinfunction "VCC_8") (pintype "bidirectional"))
      (node (ref "Z1") (pin "4") (pinfunction "VDD_4") (pintype "power_in"))
    )
    (net (code "75") (name "unconnected-(J1-ID-Pad4)") (class "Default")
      (node (ref "J1") (pin "4") (pinfunction "ID_4") (pintype "passive"))
    )
    (net (code "76") (name "unconnected-(S1A-O-Pad3)") (class "Default")
      (node (ref "S1") (pin "3") (pinfunction "O_3") (pintype "passive"))
    )
    (net (code "77") (name "unconnected-(S1B-O-Pad6)") (class "Default")
      (node (ref "S1") (pin "6") (pinfunction "O_6") (pintype "passive"))
    )
    (net (code "78") (name "unconnected-(U1-PA8-Pad41)") (class "Default")
      (node (ref "U1") (pin "41") (pinfunction "PA8_41") (pintype "bidirectional"))
    )
    (net (code "79") (name "unconnected-(U1-PA10-Pad43)") (class "Default")
      (node (ref "U1") (pin "43") (pinfunction "PA10_43") (pintype "bidirectional"))
    )
    (net (code "80") (name "unconnected-(U1-PA15-Pad50)") (class "Default")
      (node (ref "U1") (pin "50") (pinfunction "PA15_50") (pintype "bidirectional"))
    )
    (net (code "81") (name "unconnected-(U1-PB8-Pad61)") (class "Default")
      (node (ref "U1") (pin "61") (pinfunction "PB8_61") (pintype "bidirectional"))
    )
    (net (code "82") (name "unconnected-(U1-PB9-Pad62)") (class "Default")
      (node (ref "U1") (pin "62") (pinfunction "PB9_62") (pintype "bidirectional"))
    )
    (net (code "83") (name "unconnected-(U1-PC3-Pad11)") (class "Default")
      (node (ref "U1") (pin "11") (pinfunction "PC3_11") (pintype "bidirectional"))
    )
    (net (code "84") (name "unconnected-(U1-PC9-Pad40)") (class "Default")
      (node (ref "U1") (pin "40") (pinfunction "PC9_40") (pintype "bidirectional"))
    )
    (net (code "85") (name "unconnected-(U1-PC13-Pad2)") (class "Default")
      (node (ref "U1") (pin "2") (pinfunction "PC13_2") (pintype "bidirectional"))
    )
    (net (code "86") (name "unconnected-(U1-PH1-Pad6)") (class "Default")
      (node (ref "U1") (pin "6") (pinfunction "PH1_6") (pintype "bidirectional"))
    )
    (net (code "87") (name "unconnected-(U2-NC-Pad8)") (class "Default")
      (node (ref "U2") (pin "8") (pinfunction "NC_8") (pintype "no_connect"))
    )
    (net (code "88") (name "unconnected-(Z1-TRI-Pad1)") (class "Default")
      (node (ref "Z1") (pin "1") (pinfunction "TRI_1") (pintype "input"))
    )
  )
)
